# Xadow-NFC-v2.net
KiCad netlist of a schematic drawn in EAGLE
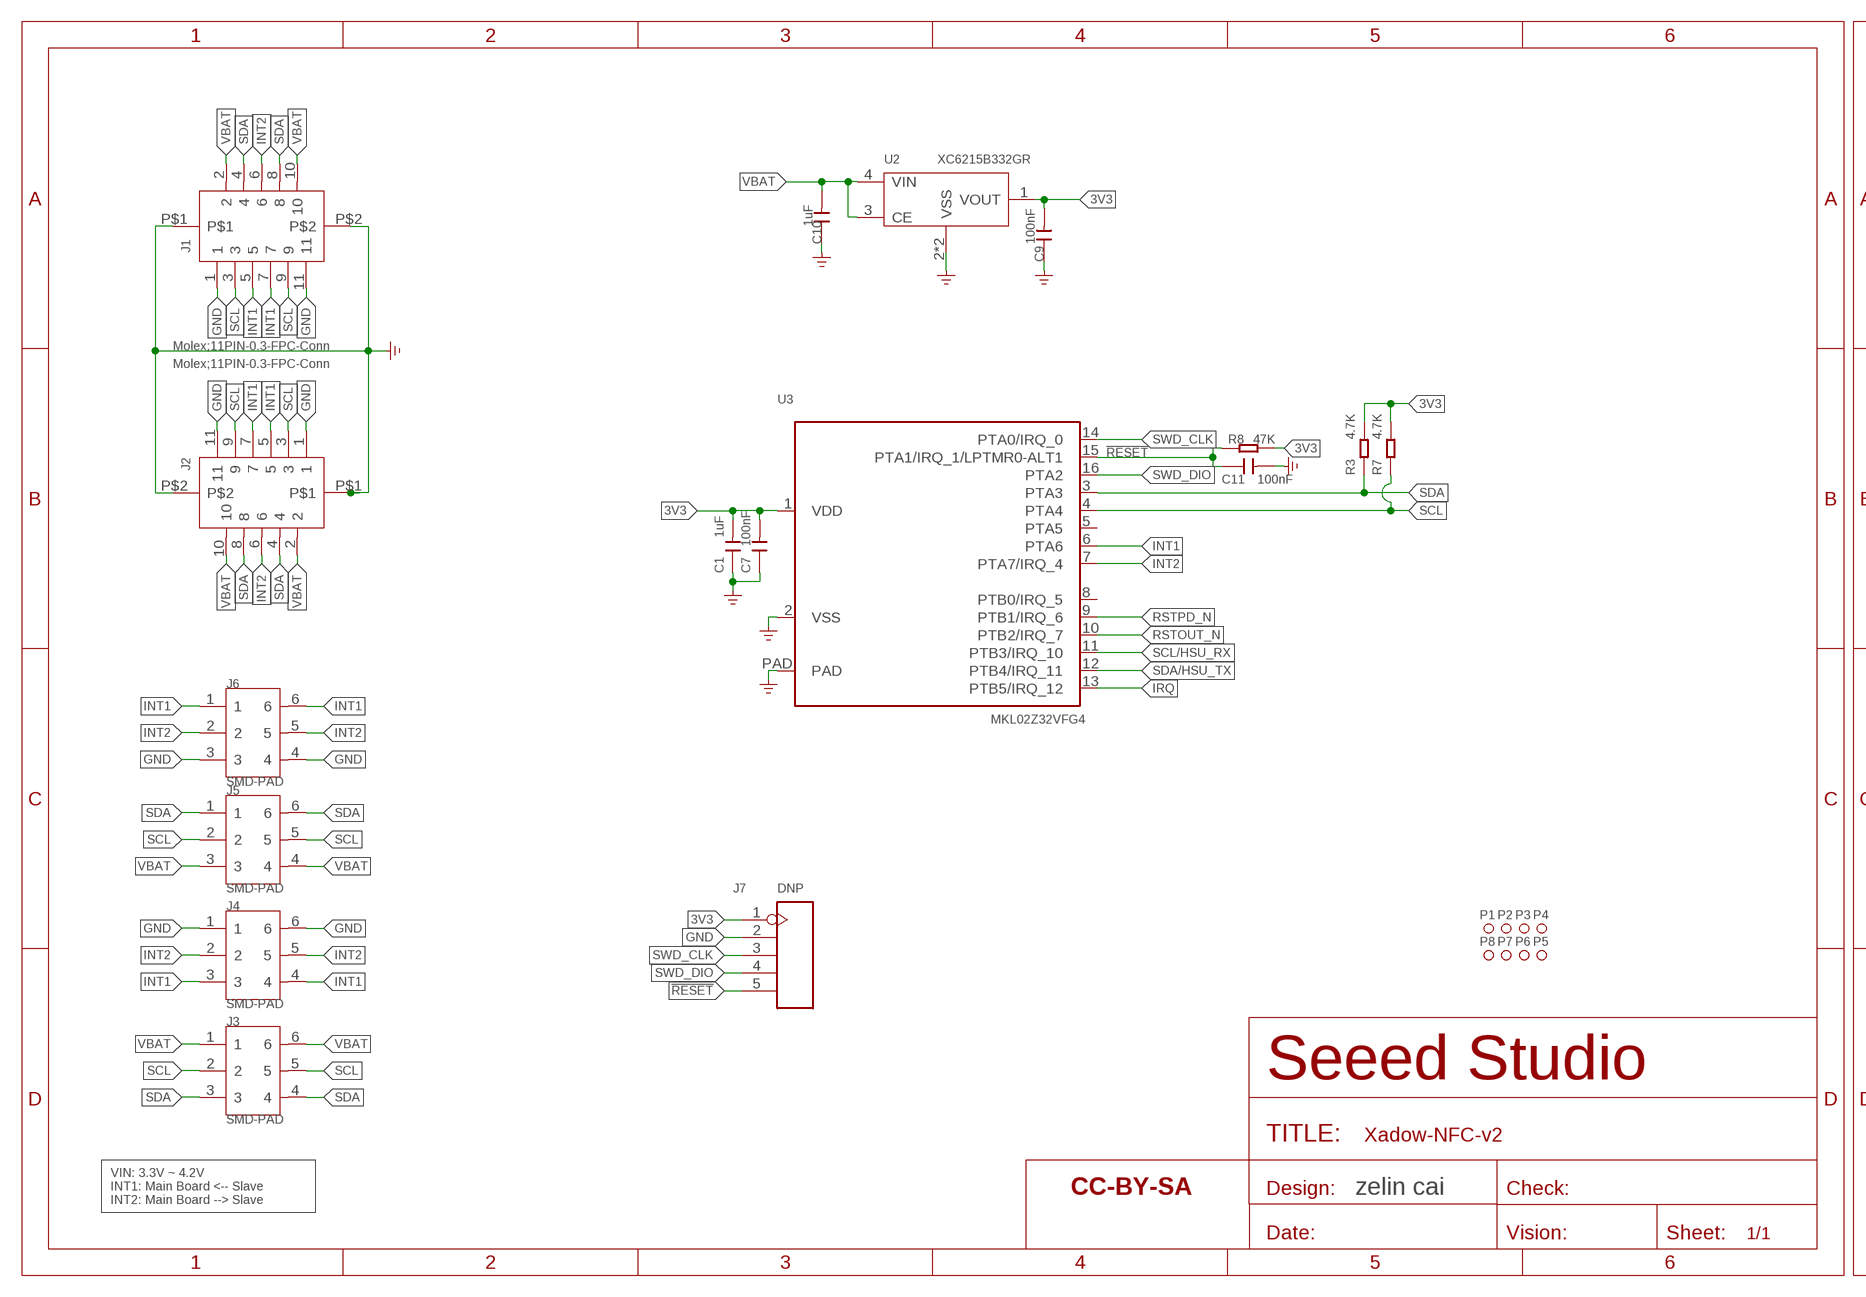
[diagram p0: schematic, sheet 1, part 1 of 2]
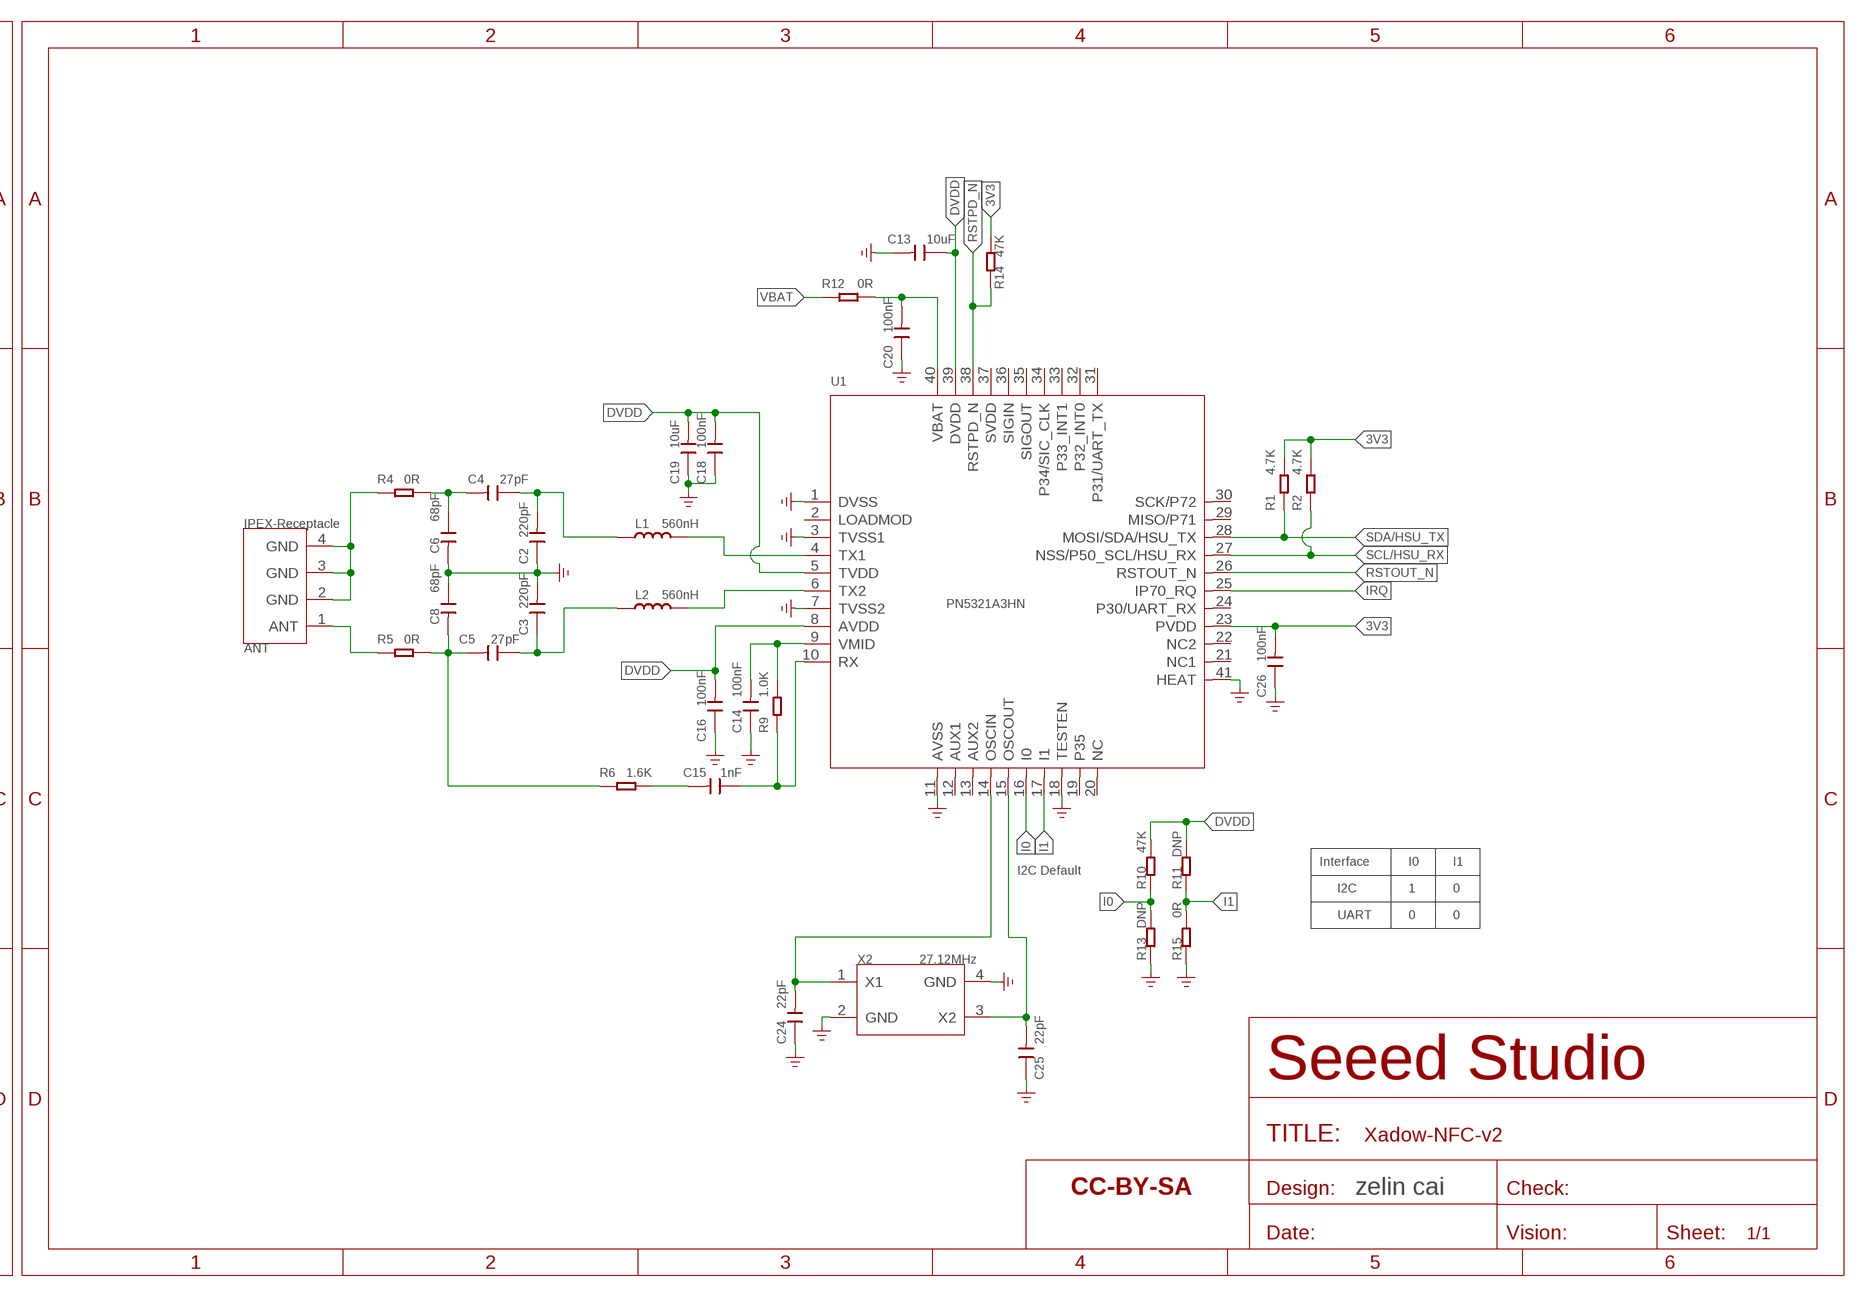
[diagram p1: schematic, sheet 1, part 2 of 2]

(export (version "E")
  (design (tool "Eeschema 10.0.6"))
  (components
    (comp (ref "ANT")
      (value "IPEX-Receptacle")
      (footprint "eagle-import:ANT-IPEX4-1.7X1.7MM")
      (libsource (lib "eagle-import") (part "ANT_IPEX"))
    )
    (comp (ref "C1")
      (value "1uF")
      (footprint "eagle-import:C0402")
      (libsource (lib "eagle-import") (part "CAP-0402"))
    )
    (comp (ref "C2")
      (value "220pF")
      (footprint "eagle-import:C0402")
      (libsource (lib "eagle-import") (part "CAP-0402"))
    )
    (comp (ref "C3")
      (value "220pF")
      (footprint "eagle-import:C0402")
      (libsource (lib "eagle-import") (part "CAP-0402"))
    )
    (comp (ref "C4")
      (value "27pF")
      (footprint "eagle-import:C0402")
      (libsource (lib "eagle-import") (part "CAP-0402"))
    )
    (comp (ref "C5")
      (value "27pF")
      (footprint "eagle-import:C0402")
      (libsource (lib "eagle-import") (part "CAP-0402"))
    )
    (comp (ref "C6")
      (value "68pF")
      (footprint "eagle-import:C0402")
      (libsource (lib "eagle-import") (part "CAP-0402"))
    )
    (comp (ref "C7")
      (value "100nF")
      (footprint "eagle-import:C0402")
      (libsource (lib "eagle-import") (part "CAP-0402"))
    )
    (comp (ref "C8")
      (value "68pF")
      (footprint "eagle-import:C0402")
      (libsource (lib "eagle-import") (part "CAP-0402"))
    )
    (comp (ref "C9")
      (value "100nF")
      (footprint "eagle-import:C0402")
      (libsource (lib "eagle-import") (part "CAP-0402"))
    )
    (comp (ref "C10")
      (value "1uF")
      (footprint "eagle-import:C0402")
      (libsource (lib "eagle-import") (part "CAP-0402"))
    )
    (comp (ref "C11")
      (value "100nF")
      (footprint "eagle-import:C0402")
      (libsource (lib "eagle-import") (part "CAP-0402"))
    )
    (comp (ref "C13")
      (value "10uF")
      (footprint "eagle-import:C0402")
      (libsource (lib "eagle-import") (part "CAP-0402"))
    )
    (comp (ref "C14")
      (value "100nF")
      (footprint "eagle-import:C0402")
      (libsource (lib "eagle-import") (part "CAP-0402"))
    )
    (comp (ref "C15")
      (value "1nF")
      (footprint "eagle-import:C0402")
      (libsource (lib "eagle-import") (part "CAP-0402"))
    )
    (comp (ref "C16")
      (value "100nF")
      (footprint "eagle-import:C0402")
      (libsource (lib "eagle-import") (part "CAP-0402"))
    )
    (comp (ref "C18")
      (value "100nF")
      (footprint "eagle-import:C0402")
      (libsource (lib "eagle-import") (part "CAP-0402"))
    )
    (comp (ref "C19")
      (value "10uF")
      (footprint "eagle-import:C0402")
      (libsource (lib "eagle-import") (part "CAP-0402"))
    )
    (comp (ref "C20")
      (value "100nF")
      (footprint "eagle-import:C0402")
      (libsource (lib "eagle-import") (part "CAP-0402"))
    )
    (comp (ref "C24")
      (value "22pF")
      (footprint "eagle-import:C0402")
      (libsource (lib "eagle-import") (part "CAP-0402"))
    )
    (comp (ref "C25")
      (value "22pF")
      (footprint "eagle-import:C0402")
      (libsource (lib "eagle-import") (part "CAP-0402"))
    )
    (comp (ref "C26")
      (value "100nF")
      (footprint "eagle-import:C0402")
      (libsource (lib "eagle-import") (part "CAP-0402"))
    )
    (comp (ref "J1")
      (value "Molex;11PIN-0.3-FPC-Conn")
      (footprint "eagle-import:FPC11-SMD-0.3(FH35C)")
      (libsource (lib "eagle-import") (part "FPC-CONNECTER-11P(FH35C-11S-0.3SHW(50))"))
    )
    (comp (ref "J2")
      (value "Molex;11PIN-0.3-FPC-Conn")
      (footprint "eagle-import:FPC11-SMD-0.3(FH35C)")
      (libsource (lib "eagle-import") (part "FPC-CONNECTER-11P(FH35C-11S-0.3SHW(50))"))
    )
    (comp (ref "J3")
      (value "SMD-PAD")
      (footprint "eagle-import:6P-DIP-2_S3")
      (libsource (lib "eagle-import") (part "HEADER6_S3"))
    )
    (comp (ref "J4")
      (value "SMD-PAD")
      (footprint "eagle-import:6P-DIP-2_ROUND")
      (libsource (lib "eagle-import") (part "HEADER6_ROUND"))
    )
    (comp (ref "J5")
      (value "SMD-PAD")
      (footprint "eagle-import:6P-DIP-2")
      (libsource (lib "eagle-import") (part "HEADER6"))
    )
    (comp (ref "J6")
      (value "SMD-PAD")
      (footprint "eagle-import:6P-DIP-2_ROUND")
      (libsource (lib "eagle-import") (part "HEADER6_ROUND"))
    )
    (comp (ref "J7")
      (value "DNP")
      (footprint "eagle-import:H5-SMD-2.0-TEST")
      (libsource (lib "eagle-import") (part "HEADER-5P'TEST'"))
    )
    (comp (ref "L1")
      (value "560nH")
      (footprint "eagle-import:L0603")
      (libsource (lib "eagle-import") (part "INDUCTOR/FERRITE-BEAD'0603'"))
    )
    (comp (ref "L2")
      (value "560nH")
      (footprint "eagle-import:L0603")
      (libsource (lib "eagle-import") (part "INDUCTOR/FERRITE-BEAD'0603'"))
    )
    (comp (ref "P1")
      (value "MRK")
      (footprint "eagle-import:ROUND-MARK-1.0")
      (fields (field (name "PARTNO") "DNP"))
      (libsource (lib "eagle-import") (part "MARK-1.0'ANNULAR'"))
    )
    (comp (ref "P2")
      (value "MRK")
      (footprint "eagle-import:ROUND-MARK-1.0")
      (fields (field (name "PARTNO") "DNP"))
      (libsource (lib "eagle-import") (part "MARK-1.0'ANNULAR'"))
    )
    (comp (ref "P3")
      (value "MRK")
      (footprint "eagle-import:ROUND-MARK-1.0")
      (fields (field (name "PARTNO") "DNP"))
      (libsource (lib "eagle-import") (part "MARK-1.0'ANNULAR'"))
    )
    (comp (ref "P4")
      (value "MRK")
      (footprint "eagle-import:ROUND-MARK-1.0")
      (fields (field (name "PARTNO") "DNP"))
      (libsource (lib "eagle-import") (part "MARK-1.0'ANNULAR'"))
    )
    (comp (ref "P5")
      (value "MRK")
      (footprint "eagle-import:ROUND-MARK-1.0")
      (fields (field (name "PARTNO") "DNP"))
      (libsource (lib "eagle-import") (part "MARK-1.0'ANNULAR'"))
    )
    (comp (ref "P6")
      (value "MRK")
      (footprint "eagle-import:ROUND-MARK-1.0")
      (fields (field (name "PARTNO") "DNP"))
      (libsource (lib "eagle-import") (part "MARK-1.0'ANNULAR'"))
    )
    (comp (ref "P7")
      (value "MRK")
      (footprint "eagle-import:ROUND-MARK-1.0")
      (fields (field (name "PARTNO") "DNP"))
      (libsource (lib "eagle-import") (part "MARK-1.0'ANNULAR'"))
    )
    (comp (ref "P8")
      (value "MRK")
      (footprint "eagle-import:ROUND-MARK-1.0")
      (fields (field (name "PARTNO") "DNP"))
      (libsource (lib "eagle-import") (part "MARK-1.0'ANNULAR'"))
    )
    (comp (ref "R1")
      (value "4.7K")
      (footprint "eagle-import:R0402")
      (libsource (lib "eagle-import") (part "RES-0402"))
    )
    (comp (ref "R2")
      (value "4.7K")
      (footprint "eagle-import:R0402")
      (libsource (lib "eagle-import") (part "RES-0402"))
    )
    (comp (ref "R3")
      (value "4.7K")
      (footprint "eagle-import:R0402")
      (libsource (lib "eagle-import") (part "RES-0402"))
    )
    (comp (ref "R4")
      (value "0R")
      (footprint "eagle-import:R0402")
      (libsource (lib "eagle-import") (part "RES-0402"))
    )
    (comp (ref "R5")
      (value "0R")
      (footprint "eagle-import:R0402")
      (libsource (lib "eagle-import") (part "RES-0402"))
    )
    (comp (ref "R6")
      (value "1.6K")
      (footprint "eagle-import:R0402")
      (libsource (lib "eagle-import") (part "RES-0402"))
    )
    (comp (ref "R7")
      (value "4.7K")
      (footprint "eagle-import:R0402")
      (libsource (lib "eagle-import") (part "RES-0402"))
    )
    (comp (ref "R8")
      (value "47K")
      (footprint "eagle-import:R0402")
      (libsource (lib "eagle-import") (part "RES-0402"))
    )
    (comp (ref "R9")
      (value "1.0K")
      (footprint "eagle-import:R0402")
      (libsource (lib "eagle-import") (part "RES-0402"))
    )
    (comp (ref "R10")
      (value "47K")
      (footprint "eagle-import:R0402")
      (libsource (lib "eagle-import") (part "RES-0402"))
    )
    (comp (ref "R11")
      (value "DNP")
      (footprint "eagle-import:R0402")
      (libsource (lib "eagle-import") (part "RES-0402"))
    )
    (comp (ref "R12")
      (value "0R")
      (footprint "eagle-import:R0402")
      (libsource (lib "eagle-import") (part "RES-0402"))
    )
    (comp (ref "R13")
      (value "DNP")
      (footprint "eagle-import:R0402")
      (libsource (lib "eagle-import") (part "RES-0402"))
    )
    (comp (ref "R14")
      (value "47K")
      (footprint "eagle-import:R0402")
      (libsource (lib "eagle-import") (part "RES-0402"))
    )
    (comp (ref "R15")
      (value "0R")
      (footprint "eagle-import:R0402")
      (libsource (lib "eagle-import") (part "RES-0402"))
    )
    (comp (ref "U$1")
      (value "PAGE1")
      (footprint "eagle-import:SEEEDSTUDIO-PCB-FRAME")
      (libsource (lib "eagle-import") (part "SEEEDSTUDIO-OPEN-SCH-FRAME"))
    )
    (comp (ref "U$21")
      (value "PAGE2")
      (footprint "eagle-import:SEEEDSTUDIO-PCB-FRAME")
      (libsource (lib "eagle-import") (part "SEEEDSTUDIO-OPEN-SCH-FRAME"))
    )
    (comp (ref "U1")
      (value "PN5321A3HN")
      (footprint "eagle-import:QFN40G-0.5-6X6MM")
      (libsource (lib "eagle-import") (part "RF-PN5321A3HN/C106,55"))
    )
    (comp (ref "U2")
      (value "XC6215B332GR")
      (footprint "eagle-import:USP4-0.6-1.2X1.6MM")
      (libsource (lib "eagle-import") (part "PMIC-XC6215-3V3"))
    )
    (comp (ref "U3")
      (value "MKL02Z32VFG4")
      (footprint "eagle-import:QFN16G-0.5-3X3MM")
      (fields (field (name "MPN") "MKL02ZxxVFG4"))
      (libsource (lib "eagle-import") (part "CONTROLLER-MKL02ZXXVFG4"))
    )
    (comp (ref "X2")
      (value "27.12MHz")
      (footprint "eagle-import:SMD4P-2.0X1.6X0.5MM")
      (libsource (lib "eagle-import") (part "CRYSTALS-4P(T384)"))
    )
  )
  (nets
    (net (code "1") (name "/SVDD") (class "Default")
      (node (ref "U1") (pin "37") (pinfunction "SVDD_37") (pintype "power_in"))
    )
    (net (code "2") (name "/~{RESET}") (class "Default")
      (node (ref "C11") (pin "1") (pinfunction "1_1") (pintype "passive"))
      (node (ref "J7") (pin "5") (pinfunction "5_5") (pintype "bidirectional"))
      (node (ref "R8") (pin "1") (pinfunction "1_1") (pintype "passive"))
      (node (ref "U3") (pin "15") (pinfunction "PTA1/IRQ_1/LPTMR0-ALT1_15") (pintype "bidirectional"))
    )
    (net (code "3") (name "3V3") (class "Default")
      (node (ref "C1") (pin "2") (pinfunction "2_2") (pintype "passive"))
      (node (ref "C26") (pin "2") (pinfunction "2_2") (pintype "passive"))
      (node (ref "C7") (pin "2") (pinfunction "2_2") (pintype "passive"))
      (node (ref "C9") (pin "2") (pinfunction "2_2") (pintype "passive"))
      (node (ref "J7") (pin "1") (pinfunction "1_1") (pintype "bidirectional"))
      (node (ref "R1") (pin "2") (pinfunction "2_2") (pintype "passive"))
      (node (ref "R14") (pin "2") (pinfunction "2_2") (pintype "passive"))
      (node (ref "R2") (pin "2") (pinfunction "2_2") (pintype "passive"))
      (node (ref "R3") (pin "2") (pinfunction "2_2") (pintype "passive"))
      (node (ref "R7") (pin "2") (pinfunction "2_2") (pintype "passive"))
      (node (ref "R8") (pin "2") (pinfunction "2_2") (pintype "passive"))
      (node (ref "U1") (pin "23") (pinfunction "PVDD_23") (pintype "power_in"))
      (node (ref "U2") (pin "1") (pinfunction "VOUT_1") (pintype "bidirectional"))
      (node (ref "U3") (pin "1") (pinfunction "VDD_1") (pintype "power_in"))
    )
    (net (code "4") (name "DVDD") (class "Default")
      (node (ref "C13") (pin "1") (pinfunction "1_1") (pintype "passive"))
      (node (ref "C16") (pin "2") (pinfunction "2_2") (pintype "passive"))
      (node (ref "C18") (pin "2") (pinfunction "2_2") (pintype "passive"))
      (node (ref "C19") (pin "2") (pinfunction "2_2") (pintype "passive"))
      (node (ref "R10") (pin "1") (pinfunction "1_1") (pintype "passive"))
      (node (ref "R11") (pin "1") (pinfunction "1_1") (pintype "passive"))
      (node (ref "U1") (pin "39") (pinfunction "DVDD_39") (pintype "power_in"))
      (node (ref "U1") (pin "5") (pinfunction "TVDD_5") (pintype "power_in"))
      (node (ref "U1") (pin "8") (pinfunction "AVDD_8") (pintype "power_in"))
    )
    (net (code "5") (name "GND") (class "Default")
      (node (ref "C1") (pin "1") (pinfunction "1_1") (pintype "passive"))
      (node (ref "C10") (pin "1") (pinfunction "1_1") (pintype "passive"))
      (node (ref "C11") (pin "2") (pinfunction "2_2") (pintype "passive"))
      (node (ref "C13") (pin "2") (pinfunction "2_2") (pintype "passive"))
      (node (ref "C14") (pin "1") (pinfunction "1_1") (pintype "passive"))
      (node (ref "C16") (pin "1") (pinfunction "1_1") (pintype "passive"))
      (node (ref "C18") (pin "1") (pinfunction "1_1") (pintype "passive"))
      (node (ref "C19") (pin "1") (pinfunction "1_1") (pintype "passive"))
      (node (ref "C2") (pin "1") (pinfunction "1_1") (pintype "passive"))
      (node (ref "C20") (pin "1") (pinfunction "1_1") (pintype "passive"))
      (node (ref "C24") (pin "1") (pinfunction "1_1") (pintype "passive"))
      (node (ref "C25") (pin "1") (pinfunction "1_1") (pintype "passive"))
      (node (ref "C26") (pin "1") (pinfunction "1_1") (pintype "passive"))
      (node (ref "C3") (pin "2") (pinfunction "2_2") (pintype "passive"))
      (node (ref "C6") (pin "2") (pinfunction "2_2") (pintype "passive"))
      (node (ref "C7") (pin "1") (pinfunction "1_1") (pintype "passive"))
      (node (ref "C8") (pin "1") (pinfunction "1_1") (pintype "passive"))
      (node (ref "C9") (pin "1") (pinfunction "1_1") (pintype "passive"))
      (node (ref "J1") (pin "1") (pinfunction "1_1") (pintype "bidirectional"))
      (node (ref "J1") (pin "11") (pinfunction "11_11") (pintype "bidirectional"))
      (node (ref "J1") (pin "P$1") (pinfunction "P$1_P$1") (pintype "bidirectional"))
      (node (ref "J1") (pin "P$2") (pinfunction "P$2_P$2") (pintype "bidirectional"))
      (node (ref "J2") (pin "1") (pinfunction "1_1") (pintype "bidirectional"))
      (node (ref "J2") (pin "11") (pinfunction "11_11") (pintype "bidirectional"))
      (node (ref "J2") (pin "P$1") (pinfunction "P$1_P$1") (pintype "bidirectional"))
      (node (ref "J2") (pin "P$2") (pinfunction "P$2_P$2") (pintype "bidirectional"))
      (node (ref "J4") (pin "1") (pinfunction "1_1") (pintype "bidirectional"))
      (node (ref "J4") (pin "6") (pinfunction "6_6") (pintype "bidirectional"))
      (node (ref "J6") (pin "3") (pinfunction "3_3") (pintype "bidirectional"))
      (node (ref "J6") (pin "4") (pinfunction "4_4") (pintype "bidirectional"))
      (node (ref "J7") (pin "2") (pinfunction "2_2") (pintype "bidirectional"))
      (node (ref "R13") (pin "2") (pinfunction "2_2") (pintype "passive"))
      (node (ref "R15") (pin "2") (pinfunction "2_2") (pintype "passive"))
      (node (ref "U1") (pin "1") (pinfunction "DVSS_1") (pintype "power_in"))
      (node (ref "U1") (pin "11") (pinfunction "AVSS_11") (pintype "power_in"))
      (node (ref "U1") (pin "18") (pinfunction "TESTEN_18") (pintype "input"))
      (node (ref "U1") (pin "3") (pinfunction "TVSS1_3") (pintype "power_in"))
      (node (ref "U1") (pin "41") (pinfunction "HEAT_41") (pintype "bidirectional"))
      (node (ref "U1") (pin "7") (pinfunction "TVSS2_7") (pintype "power_in"))
      (node (ref "U2") (pin "2") (pinfunction "VSS_2") (pintype "bidirectional"))
      (node (ref "U2") (pin "PAD") (pinfunction "VSS_PAD") (pintype "bidirectional"))
      (node (ref "U3") (pin "2") (pinfunction "VSS_2") (pintype "power_in"))
      (node (ref "U3") (pin "PAD") (pinfunction "PAD_PAD") (pintype "power_in"))
      (node (ref "X2") (pin "2") (pinfunction "GND_2") (pintype "bidirectional"))
      (node (ref "X2") (pin "4") (pinfunction "GND_4") (pintype "bidirectional"))
    )
    (net (code "6") (name "I0") (class "Default")
      (node (ref "R10") (pin "2") (pinfunction "2_2") (pintype "passive"))
      (node (ref "R13") (pin "1") (pinfunction "1_1") (pintype "passive"))
      (node (ref "U1") (pin "16") (pinfunction "I0_16") (pintype "input"))
    )
    (net (code "7") (name "I1") (class "Default")
      (node (ref "R11") (pin "2") (pinfunction "2_2") (pintype "passive"))
      (node (ref "R15") (pin "1") (pinfunction "1_1") (pintype "passive"))
      (node (ref "U1") (pin "17") (pinfunction "I1_17") (pintype "input"))
    )
    (net (code "8") (name "INT1") (class "Default")
      (node (ref "J1") (pin "5") (pinfunction "5_5") (pintype "bidirectional"))
      (node (ref "J1") (pin "7") (pinfunction "7_7") (pintype "bidirectional"))
      (node (ref "J2") (pin "5") (pinfunction "5_5") (pintype "bidirectional"))
      (node (ref "J2") (pin "7") (pinfunction "7_7") (pintype "bidirectional"))
      (node (ref "J4") (pin "3") (pinfunction "3_3") (pintype "bidirectional"))
      (node (ref "J4") (pin "4") (pinfunction "4_4") (pintype "bidirectional"))
      (node (ref "J6") (pin "1") (pinfunction "1_1") (pintype "bidirectional"))
      (node (ref "J6") (pin "6") (pinfunction "6_6") (pintype "bidirectional"))
      (node (ref "U3") (pin "6") (pinfunction "PTA6_6") (pintype "bidirectional"))
    )
    (net (code "9") (name "INT2") (class "Default")
      (node (ref "J1") (pin "6") (pinfunction "6_6") (pintype "bidirectional"))
      (node (ref "J2") (pin "6") (pinfunction "6_6") (pintype "bidirectional"))
      (node (ref "J4") (pin "2") (pinfunction "2_2") (pintype "bidirectional"))
      (node (ref "J4") (pin "5") (pinfunction "5_5") (pintype "bidirectional"))
      (node (ref "J6") (pin "2") (pinfunction "2_2") (pintype "bidirectional"))
      (node (ref "J6") (pin "5") (pinfunction "5_5") (pintype "bidirectional"))
      (node (ref "U3") (pin "7") (pinfunction "PTA7/IRQ_4_7") (pintype "bidirectional"))
    )
    (net (code "10") (name "IRQ") (class "Default")
      (node (ref "U1") (pin "25") (pinfunction "IP70_RQ_25") (pintype "output"))
      (node (ref "U3") (pin "13") (pinfunction "PTB5/IRQ_12_13") (pintype "bidirectional"))
    )
    (net (code "11") (name "Net-(ANT-ANT)") (class "Default")
      (node (ref "ANT") (pin "1") (pinfunction "ANT_1") (pintype "bidirectional"))
      (node (ref "R5") (pin "1") (pinfunction "1_1") (pintype "passive"))
    )
    (net (code "12") (name "Net-(ANT-GND-Pad2)") (class "Default")
      (node (ref "ANT") (pin "2") (pinfunction "GND_2") (pintype "bidirectional"))
      (node (ref "ANT") (pin "3") (pinfunction "GND_3") (pintype "bidirectional"))
      (node (ref "ANT") (pin "4") (pinfunction "GND_4") (pintype "bidirectional"))
      (node (ref "R4") (pin "1") (pinfunction "1_1") (pintype "passive"))
    )
    (net (code "13") (name "Net-(C2-Pad2)") (class "Default")
      (node (ref "C2") (pin "2") (pinfunction "2_2") (pintype "passive"))
      (node (ref "C4") (pin "1") (pinfunction "1_1") (pintype "passive"))
      (node (ref "L1") (pin "1") (pinfunction "1_1") (pintype "passive"))
    )
    (net (code "14") (name "Net-(C3-Pad1)") (class "Default")
      (node (ref "C3") (pin "1") (pinfunction "1_1") (pintype "passive"))
      (node (ref "C5") (pin "1") (pinfunction "1_1") (pintype "passive"))
      (node (ref "L2") (pin "1") (pinfunction "1_1") (pintype "passive"))
    )
    (net (code "15") (name "Net-(C4-Pad2)") (class "Default")
      (node (ref "C4") (pin "2") (pinfunction "2_2") (pintype "passive"))
      (node (ref "C6") (pin "1") (pinfunction "1_1") (pintype "passive"))
      (node (ref "R4") (pin "2") (pinfunction "2_2") (pintype "passive"))
    )
    (net (code "16") (name "Net-(C5-Pad2)") (class "Default")
      (node (ref "C5") (pin "2") (pinfunction "2_2") (pintype "passive"))
      (node (ref "C8") (pin "2") (pinfunction "2_2") (pintype "passive"))
      (node (ref "R5") (pin "2") (pinfunction "2_2") (pintype "passive"))
      (node (ref "R6") (pin "1") (pinfunction "1_1") (pintype "passive"))
    )
    (net (code "17") (name "Net-(C15-Pad2)") (class "Default")
      (node (ref "C15") (pin "2") (pinfunction "2_2") (pintype "passive"))
      (node (ref "R6") (pin "2") (pinfunction "2_2") (pintype "passive"))
    )
    (net (code "18") (name "Net-(U1-OSCIN)") (class "Default")
      (node (ref "C24") (pin "2") (pinfunction "2_2") (pintype "passive"))
      (node (ref "U1") (pin "14") (pinfunction "OSCIN_14") (pintype "input"))
      (node (ref "X2") (pin "1") (pinfunction "X1_1") (pintype "bidirectional"))
    )
    (net (code "19") (name "Net-(U1-OSCOUT)") (class "Default")
      (node (ref "C25") (pin "2") (pinfunction "2_2") (pintype "passive"))
      (node (ref "U1") (pin "15") (pinfunction "OSCOUT_15") (pintype "output"))
      (node (ref "X2") (pin "3") (pinfunction "X2_3") (pintype "bidirectional"))
    )
    (net (code "20") (name "Net-(U1-RX)") (class "Default")
      (node (ref "C15") (pin "1") (pinfunction "1_1") (pintype "passive"))
      (node (ref "R9") (pin "1") (pinfunction "1_1") (pintype "passive"))
      (node (ref "U1") (pin "10") (pinfunction "RX_10") (pintype "input"))
    )
    (net (code "21") (name "Net-(U1-TX1)") (class "Default")
      (node (ref "L1") (pin "2") (pinfunction "2_2") (pintype "passive"))
      (node (ref "U1") (pin "4") (pinfunction "TX1_4") (pintype "output"))
    )
    (net (code "22") (name "Net-(U1-TX2)") (class "Default")
      (node (ref "L2") (pin "2") (pinfunction "2_2") (pintype "passive"))
      (node (ref "U1") (pin "6") (pinfunction "TX2_6") (pintype "output"))
    )
    (net (code "23") (name "Net-(U1-VMID)") (class "Default")
      (node (ref "C14") (pin "2") (pinfunction "2_2") (pintype "passive"))
      (node (ref "R9") (pin "2") (pinfunction "2_2") (pintype "passive"))
      (node (ref "U1") (pin "9") (pinfunction "VMID_9") (pintype "output"))
    )
    (net (code "24") (name "RSTOUT_N") (class "Default")
      (node (ref "U1") (pin "26") (pinfunction "RSTOUT_N_26") (pintype "bidirectional"))
      (node (ref "U3") (pin "10") (pinfunction "PTB2/IRQ_7_10") (pintype "bidirectional"))
    )
    (net (code "25") (name "RSTPD_N") (class "Default")
      (node (ref "R14") (pin "1") (pinfunction "1_1") (pintype "passive"))
      (node (ref "U1") (pin "38") (pinfunction "RSTPD_N_38") (pintype "input"))
      (node (ref "U3") (pin "9") (pinfunction "PTB1/IRQ_6_9") (pintype "bidirectional"))
    )
    (net (code "26") (name "SCL") (class "Default")
      (node (ref "J1") (pin "3") (pinfunction "3_3") (pintype "bidirectional"))
      (node (ref "J1") (pin "9") (pinfunction "9_9") (pintype "bidirectional"))
      (node (ref "J2") (pin "3") (pinfunction "3_3") (pintype "bidirectional"))
      (node (ref "J2") (pin "9") (pinfunction "9_9") (pintype "bidirectional"))
      (node (ref "J3") (pin "2") (pinfunction "2_2") (pintype "bidirectional"))
      (node (ref "J3") (pin "5") (pinfunction "5_5") (pintype "bidirectional"))
      (node (ref "J5") (pin "2") (pinfunction "2_2") (pintype "bidirectional"))
      (node (ref "J5") (pin "5") (pinfunction "5_5") (pintype "bidirectional"))
      (node (ref "R7") (pin "1") (pinfunction "1_1") (pintype "passive"))
      (node (ref "U3") (pin "4") (pinfunction "PTA4_4") (pintype "bidirectional"))
    )
    (net (code "27") (name "SCL{slash}HSU_RX") (class "Default")
      (node (ref "R2") (pin "1") (pinfunction "1_1") (pintype "passive"))
      (node (ref "U1") (pin "27") (pinfunction "NSS/P50_SCL/HSU_RX_27") (pintype "bidirectional"))
      (node (ref "U3") (pin "11") (pinfunction "PTB3/IRQ_10_11") (pintype "bidirectional"))
    )
    (net (code "28") (name "SDA") (class "Default")
      (node (ref "J1") (pin "4") (pinfunction "4_4") (pintype "bidirectional"))
      (node (ref "J1") (pin "8") (pinfunction "8_8") (pintype "bidirectional"))
      (node (ref "J2") (pin "4") (pinfunction "4_4") (pintype "bidirectional"))
      (node (ref "J2") (pin "8") (pinfunction "8_8") (pintype "bidirectional"))
      (node (ref "J3") (pin "3") (pinfunction "3_3") (pintype "bidirectional"))
      (node (ref "J3") (pin "4") (pinfunction "4_4") (pintype "bidirectional"))
      (node (ref "J5") (pin "1") (pinfunction "1_1") (pintype "bidirectional"))
      (node (ref "J5") (pin "6") (pinfunction "6_6") (pintype "bidirectional"))
      (node (ref "R3") (pin "1") (pinfunction "1_1") (pintype "passive"))
      (node (ref "U3") (pin "3") (pinfunction "PTA3_3") (pintype "bidirectional"))
    )
    (net (code "29") (name "SDA{slash}HSU_TX") (class "Default")
      (node (ref "R1") (pin "1") (pinfunction "1_1") (pintype "passive"))
      (node (ref "U1") (pin "28") (pinfunction "MOSI/SDA/HSU_TX_28") (pintype "bidirectional"))
      (node (ref "U3") (pin "12") (pinfunction "PTB4/IRQ_11_12") (pintype "bidirectional"))
    )
    (net (code "30") (name "SWD_CLK") (class "Default")
      (node (ref "J7") (pin "3") (pinfunction "3_3") (pintype "bidirectional"))
      (node (ref "U3") (pin "14") (pinfunction "PTA0/IRQ_0_14") (pintype "bidirectional"))
    )
    (net (code "31") (name "SWD_DIO") (class "Default")
      (node (ref "J7") (pin "4") (pinfunction "4_4") (pintype "bidirectional"))
      (node (ref "U3") (pin "16") (pinfunction "PTA2_16") (pintype "bidirectional"))
    )
    (net (code "32") (name "VBAT") (class "Default")
      (node (ref "C10") (pin "2") (pinfunction "2_2") (pintype "passive"))
      (node (ref "C20") (pin "2") (pinfunction "2_2") (pintype "passive"))
      (node (ref "J1") (pin "10") (pinfunction "10_10") (pintype "bidirectional"))
      (node (ref "J1") (pin "2") (pinfunction "2_2") (pintype "bidirectional"))
      (node (ref "J2") (pin "10") (pinfunction "10_10") (pintype "bidirectional"))
      (node (ref "J2") (pin "2") (pinfunction "2_2") (pintype "bidirectional"))
      (node (ref "J3") (pin "1") (pinfunction "1_1") (pintype "bidirectional"))
      (node (ref "J3") (pin "6") (pinfunction "6_6") (pintype "bidirectional"))
      (node (ref "J5") (pin "3") (pinfunction "3_3") (pintype "bidirectional"))
      (node (ref "J5") (pin "4") (pinfunction "4_4") (pintype "bidirectional"))
      (node (ref "R12") (pin "1") (pinfunction "1_1") (pintype "passive"))
      (node (ref "R12") (pin "2") (pinfunction "2_2") (pintype "passive"))
      (node (ref "U1") (pin "40") (pinfunction "VBAT_40") (pintype "power_in"))
      (node (ref "U2") (pin "3") (pinfunction "CE_3") (pintype "bidirectional"))
      (node (ref "U2") (pin "4") (pinfunction "VIN_4") (pintype "bidirectional"))
    )
    (net (code "33") (name "unconnected-(U1-AUX1-Pad12)") (class "Default")
      (node (ref "U1") (pin "12") (pinfunction "AUX1_12") (pintype "output"))
    )
    (net (code "34") (name "unconnected-(U1-AUX2-Pad13)") (class "Default")
      (node (ref "U1") (pin "13") (pinfunction "AUX2_13") (pintype "output"))
    )
    (net (code "35") (name "unconnected-(U1-LOADMOD-Pad2)") (class "Default")
      (node (ref "U1") (pin "2") (pinfunction "LOADMOD_2") (pintype "output"))
    )
    (net (code "36") (name "unconnected-(U1-MISO{slash}P71-Pad29)") (class "Default")
      (node (ref "U1") (pin "29") (pinfunction "MISO/P71_29") (pintype "bidirectional"))
    )
    (net (code "37") (name "unconnected-(U1-NC-Pad20)") (class "Default")
      (node (ref "U1") (pin "20") (pinfunction "NC_20") (pintype "no_connect"))
    )
    (net (code "38") (name "unconnected-(U1-NC1-Pad21)") (class "Default")
      (node (ref "U1") (pin "21") (pinfunction "NC1_21") (pintype "no_connect"))
    )
    (net (code "39") (name "unconnected-(U1-NC2-Pad22)") (class "Default")
      (node (ref "U1") (pin "22") (pinfunction "NC2_22") (pintype "no_connect"))
    )
    (net (code "40") (name "unconnected-(U1-P30{slash}UART_RX-Pad24)") (class "Default")
      (node (ref "U1") (pin "24") (pinfunction "P30/UART_RX_24") (pintype "bidirectional"))
    )
    (net (code "41") (name "unconnected-(U1-P31{slash}UART_TX-Pad31)") (class "Default")
      (node (ref "U1") (pin "31") (pinfunction "P31/UART_TX_31") (pintype "bidirectional"))
    )
    (net (code "42") (name "unconnected-(U1-P32_INT0-Pad32)") (class "Default")
      (node (ref "U1") (pin "32") (pinfunction "P32_INT0_32") (pintype "bidirectional"))
    )
    (net (code "43") (name "unconnected-(U1-P33_INT1-Pad33)") (class "Default")
      (node (ref "U1") (pin "33") (pinfunction "P33_INT1_33") (pintype "bidirectional"))
    )
    (net (code "44") (name "unconnected-(U1-P34{slash}SIC_CLK-Pad34)") (class "Default")
      (node (ref "U1") (pin "34") (pinfunction "P34/SIC_CLK_34") (pintype "bidirectional"))
    )
    (net (code "45") (name "unconnected-(U1-P35-Pad19)") (class "Default")
      (node (ref "U1") (pin "19") (pinfunction "P35_19") (pintype "bidirectional"))
    )
    (net (code "46") (name "unconnected-(U1-SCK{slash}P72-Pad30)") (class "Default")
      (node (ref "U1") (pin "30") (pinfunction "SCK/P72_30") (pintype "bidirectional"))
    )
    (net (code "47") (name "unconnected-(U1-SIGIN-Pad36)") (class "Default")
      (node (ref "U1") (pin "36") (pinfunction "SIGIN_36") (pintype "input"))
    )
    (net (code "48") (name "unconnected-(U1-SIGOUT-Pad35)") (class "Default")
      (node (ref "U1") (pin "35") (pinfunction "SIGOUT_35") (pintype "output"))
    )
    (net (code "49") (name "unconnected-(U3-PTA5-Pad5)") (class "Default")
      (node (ref "U3") (pin "5") (pinfunction "PTA5_5") (pintype "bidirectional"))
    )
    (net (code "50") (name "unconnected-(U3-PTB0{slash}IRQ_5-Pad8)") (class "Default")
      (node (ref "U3") (pin "8") (pinfunction "PTB0/IRQ_5_8") (pintype "bidirectional"))
    )
  )
)
